# Esquematico.net
KiCad netlist of a schematic drawn in Altium Designer
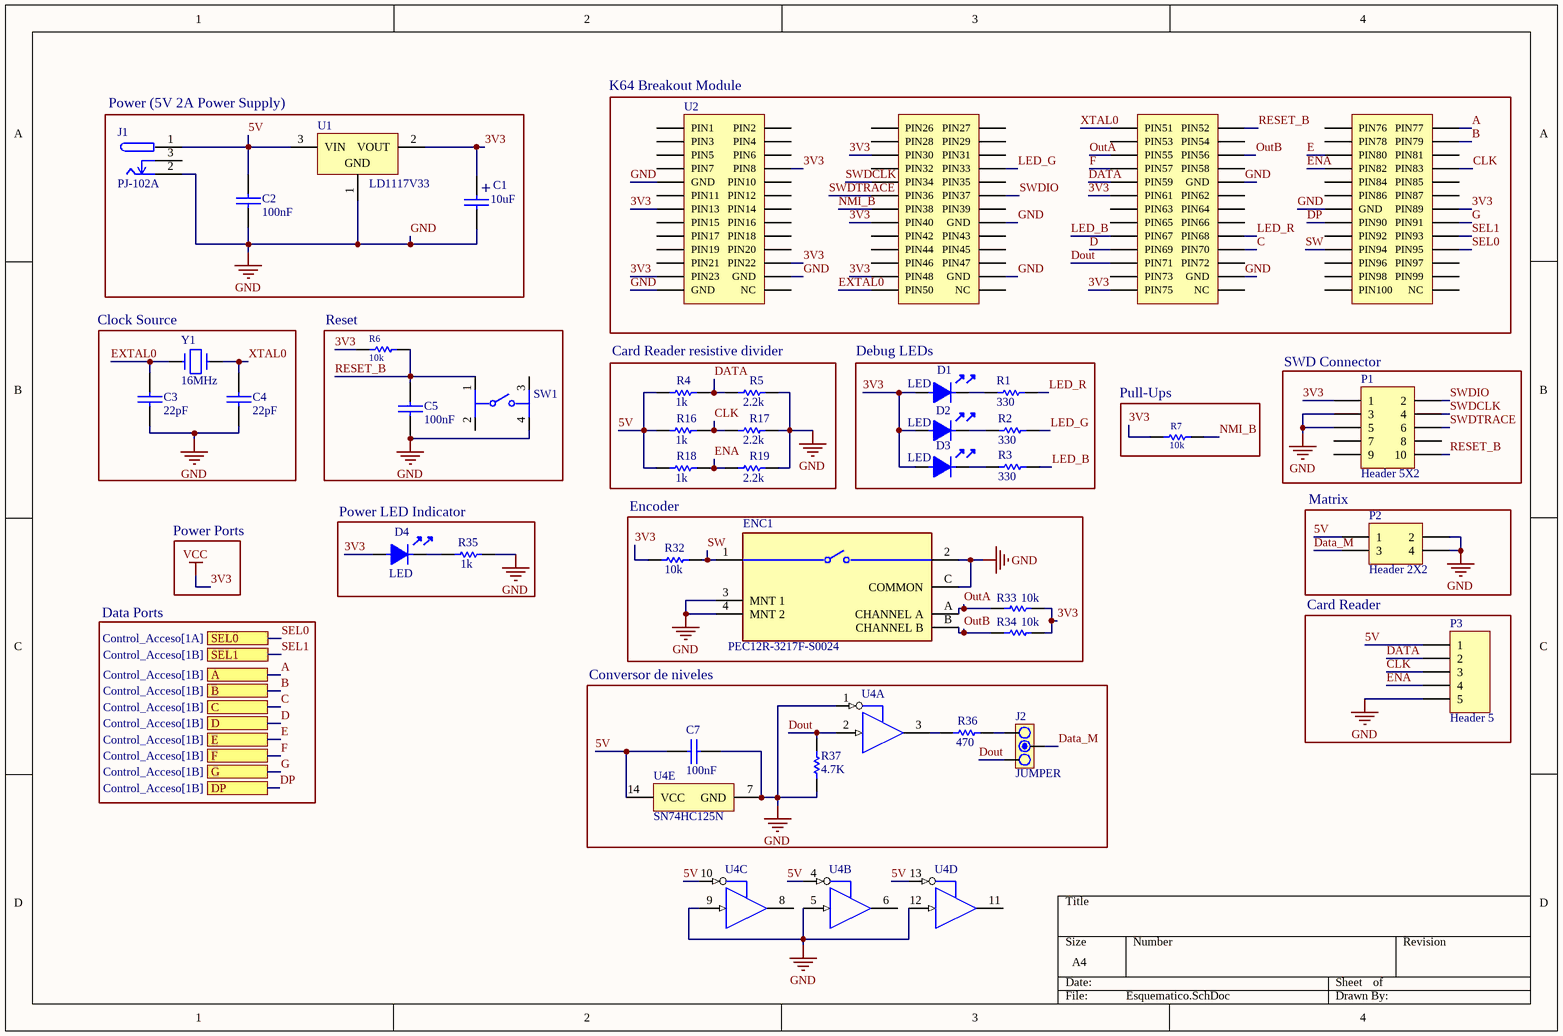
[diagram p0: Esquematico.SchDoc]

(export (version "E")
  (design (tool "Eeschema 10.0.6"))
  (components
    (comp (ref "C1")
      (value "10uF")
      (footprint "CAP100RP")
      (description "Electrolytic Capacitor")
      (libsource (lib "LIB PIO IX") (part "CAPPOL"))
    )
    (comp (ref "C2")
      (value "100nF")
      (footprint "CAP200")
      (description "Multilayer Ceramic Capacitor")
      (libsource (lib "LIB PIO IX") (part "CAP"))
    )
    (comp (ref "C3")
      (value "22pF")
      (footprint "CAP200")
      (description "Multilayer Ceramic Capacitor")
      (libsource (lib "LIB PIO IX") (part "CAP"))
    )
    (comp (ref "C4")
      (value "22pF")
      (footprint "CAP200")
      (description "Multilayer Ceramic Capacitor")
      (libsource (lib "LIB PIO IX") (part "CAP"))
    )
    (comp (ref "C5")
      (value "100nF")
      (footprint "CAP200")
      (description "Multilayer Ceramic Capacitor")
      (libsource (lib "LIB PIO IX") (part "CAP"))
    )
    (comp (ref "C7")
      (value "100nF")
      (footprint "CAP200")
      (description "Multilayer Ceramic Capacitor")
      (libsource (lib "LIB PIO IX") (part "CAP"))
    )
    (comp (ref "D1")
      (value "LED")
      (footprint "LED3")
      (description "3mm LED RED")
      (libsource (lib "LIB PIO IX") (part "LED"))
    )
    (comp (ref "D2")
      (value "LED")
      (footprint "LED3")
      (description "3mm LED GREEN")
      (libsource (lib "LIB PIO IX") (part "LED"))
    )
    (comp (ref "D3")
      (value "LED")
      (footprint "LED3")
      (description "3mm LED BLUE")
      (libsource (lib "LIB PIO IX") (part "LED"))
    )
    (comp (ref "D4")
      (value "LED")
      (footprint "LED3")
      (description "3mm LED RED")
      (libsource (lib "LIB PIO IX") (part "LED"))
    )
    (comp (ref "ENC1")
      (value "PEC12R-3217F-S0024")
      (footprint "FP-PEC12R-3217F-S0024-MFG")
      (description "ROTARY ENCODER")
      (libsource (lib "Altium Content Vault") (part "795c46dd6d7d77f565e7c060d07d204"))
    )
    (comp (ref "J1")
      (value "PJ-102A")
      (footprint "FP-PJ-102A-MFG")
      (description "PJ-102A 2.0 x 6.5 mm, 2.5 A, Horizontal, Through Hole, Tapered Pins, Dc Power Jack Connector")
      (libsource (lib "Altium Content Vault") (part "c639f672d24b5d70918fa8d934b95d1"))
    )
    (comp (ref "J2") (value "JUMPER") (footprint "JUMPER3") (libsource (lib "LIB PIO IX") (part "JUMPER3")))
    (comp (ref "P1")
      (value "Header 5X2")
      (footprint "HDR2X5")
      (description "Header, 5-Pin, Dual row")
      (fields (field (name "PUBLISHER") "Altium Limited"))
      (libsource (lib "Miscellaneous Connectors") (part "Header 5X2"))
    )
    (comp (ref "P2")
      (value "Header 2X2")
      (footprint "HDR2X2")
      (description "Header, 2-Pin, Dual row")
      (fields (field (name "PUBLISHER") "Altium Limited"))
      (libsource (lib "Miscellaneous Connectors") (part "Header 2X2"))
    )
    (comp (ref "P3")
      (value "Header 5")
      (footprint "HDR1X5")
      (description "Header, 5-Pin")
      (fields (field (name "PUBLISHER") "Altium Limited"))
      (libsource (lib "Miscellaneous Connectors") (part "Header 5"))
    )
    (comp (ref "R1")
      (value "330")
      (footprint "RES400")
      (description "Through Hole Resistor 1/8W Carbon Film")
      (libsource (lib "LIB PIO IX") (part "RES"))
    )
    (comp (ref "R2")
      (value "330")
      (footprint "RES400")
      (description "Through Hole Resistor 1/8W Carbon Film")
      (libsource (lib "LIB PIO IX") (part "RES"))
    )
    (comp (ref "R3")
      (value "330")
      (footprint "RES400")
      (description "Through Hole Resistor 1/8W Carbon Film")
      (libsource (lib "LIB PIO IX") (part "RES"))
    )
    (comp (ref "R4")
      (value "1k")
      (footprint "RES400")
      (description "Through Hole Resistor 1/8W Carbon Film")
      (libsource (lib "LIB PIO IX") (part "RES"))
    )
    (comp (ref "R5")
      (value "2.2k")
      (footprint "RES400")
      (description "Through Hole Resistor 1/8W Carbon Film")
      (libsource (lib "LIB PIO IX") (part "RES"))
    )
    (comp (ref "R6")
      (value "10k")
      (footprint "RES400")
      (description "Through Hole Resistor 1/8W Carbon Film")
      (libsource (lib "LIB PIO IX") (part "RES"))
    )
    (comp (ref "R7")
      (value "10k")
      (footprint "RES400")
      (description "Through Hole Resistor 1/8W Carbon Film")
      (libsource (lib "LIB PIO IX") (part "RES"))
    )
    (comp (ref "R16")
      (value "1k")
      (footprint "RES400")
      (description "Through Hole Resistor 1/8W Carbon Film")
      (libsource (lib "LIB PIO IX") (part "RES"))
    )
    (comp (ref "R17")
      (value "2.2k")
      (footprint "RES400")
      (description "Through Hole Resistor 1/8W Carbon Film")
      (libsource (lib "LIB PIO IX") (part "RES"))
    )
    (comp (ref "R18")
      (value "1k")
      (footprint "RES400")
      (description "Through Hole Resistor 1/8W Carbon Film")
      (libsource (lib "LIB PIO IX") (part "RES"))
    )
    (comp (ref "R19")
      (value "2.2k")
      (footprint "RES400")
      (description "Through Hole Resistor 1/8W Carbon Film")
      (libsource (lib "LIB PIO IX") (part "RES"))
    )
    (comp (ref "R32")
      (value "10k")
      (footprint "RES400")
      (description "Through Hole Resistor 1/8W Carbon Film")
      (libsource (lib "LIB PIO IX") (part "RES"))
    )
    (comp (ref "R33")
      (value "10k")
      (footprint "RES400")
      (description "Through Hole Resistor 1/8W Carbon Film")
      (libsource (lib "LIB PIO IX") (part "RES"))
    )
    (comp (ref "R34")
      (value "10k")
      (footprint "RES400")
      (description "Through Hole Resistor 1/8W Carbon Film")
      (libsource (lib "LIB PIO IX") (part "RES"))
    )
    (comp (ref "R35")
      (value "1k")
      (footprint "RES400")
      (description "Through Hole Resistor 1/8W Carbon Film")
      (libsource (lib "LIB PIO IX") (part "RES"))
    )
    (comp (ref "R36")
      (value "470")
      (footprint "RES400")
      (description "Through Hole Resistor 1/8W Carbon Film")
      (libsource (lib "LIB PIO IX") (part "RES"))
    )
    (comp (ref "R37")
      (value "4.7K")
      (footprint "RES400")
      (description "Through Hole Resistor 1/8W Carbon Film")
      (libsource (lib "LIB PIO IX") (part "RES"))
    )
    (comp (ref "SW1")
      (value "~")
      (footprint "FP-B3F-1055-MFG")
      (description "SWITCH TACTILE SPST-NO 0.05A 24V")
      (libsource (lib "Altium Content Vault") (part "b8895f3f4cefb76e1819d2863dba89b"))
    )
    (comp (ref "U1")
      (value "LD1117V33")
      (footprint "TO220")
      (description "Fixed Low Drop Positive Voltage Regulator, 3.3V, 3-Pin TO-220")
      (libsource (lib "Altium Content Vault") (part "PM-REG-LD1117V-SIL3"))
    )
    (comp (ref "U2")
      (value "K64 Breakout Module")
      (footprint "Breakout")
      (description "Breakout Module Socket")
      (libsource (lib "Breakout_Module") (part "Breakout"))
    )
    (comp (ref "U4")
      (value "SN74HC125N")
      (footprint "N0014A")
      (description "Quadruple Bus Buffer Gates With 3-State Outputs, N0014A, TUBE")
      (fields
        (field (name "GENERIC PART NUMBER") "SN74HC125")
        (field (name "MANUFACTURER") "Texas Instruments")
      )
      (libsource (lib "Altium Content Vault") (part "TI-SN74HC125-N0014A-14"))
    )
    (comp (ref "Y1")
      (value "16MHz")
      (footprint "CRISTAL PERFIL")
      (description "Cristal 16MHz")
      (libsource (lib "LIB PIO IX") (part "CRISTAL"))
    )
  )
  (nets
    (net (code "1") (name "/5V") (class "Default")
      (node (ref "C2") (pin "1") (pinfunction "1_1") (pintype "passive"))
      (node (ref "C7") (pin "1") (pinfunction "1_1") (pintype "passive"))
      (node (ref "J1") (pin "1") (pinfunction "1_1") (pintype "passive"))
      (node (ref "P2") (pin "1") (pinfunction "1_1") (pintype "passive"))
      (node (ref "P3") (pin "1") (pinfunction "1_1") (pintype "passive"))
      (node (ref "R16") (pin "1") (pinfunction "1_1") (pintype "passive"))
      (node (ref "R18") (pin "1") (pinfunction "1_1") (pintype "passive"))
      (node (ref "R4") (pin "1") (pinfunction "1_1") (pintype "passive"))
      (node (ref "U1") (pin "3") (pinfunction "VIN_3") (pintype "power_in"))
      (node (ref "U4") (pin "10") (pinfunction "3~{OE}_10") (pintype "input"))
      (node (ref "U4") (pin "13") (pinfunction "4~{OE}_13") (pintype "input"))
      (node (ref "U4") (pin "14") (pinfunction "VCC_14") (pintype "power_in"))
      (node (ref "U4") (pin "4") (pinfunction "2~{OE}_4") (pintype "input"))
    )
    (net (code "2") (name "/A") (class "Default")
      (node (ref "U2") (pin "80") (pinfunction "PIN77_80") (pintype "passive"))
    )
    (net (code "3") (name "/B") (class "Default")
      (node (ref "U2") (pin "82") (pinfunction "PIN79_82") (pintype "passive"))
    )
    (net (code "4") (name "/C") (class "Default")
      (node (ref "U2") (pin "72") (pinfunction "PIN70_72") (pintype "passive"))
    )
    (net (code "5") (name "/CLK") (class "Default")
      (node (ref "P3") (pin "3") (pinfunction "3_3") (pintype "passive"))
      (node (ref "R16") (pin "2") (pinfunction "2_2") (pintype "passive"))
      (node (ref "R17") (pin "1") (pinfunction "1_1") (pintype "passive"))
      (node (ref "U2") (pin "86") (pinfunction "PIN83_86") (pintype "passive"))
    )
    (net (code "6") (name "/D") (class "Default")
      (node (ref "U2") (pin "71") (pinfunction "PIN69_71") (pintype "passive"))
    )
    (net (code "7") (name "/DATA") (class "Default")
      (node (ref "P3") (pin "2") (pinfunction "2_2") (pintype "passive"))
      (node (ref "R4") (pin "2") (pinfunction "2_2") (pintype "passive"))
      (node (ref "R5") (pin "1") (pinfunction "1_1") (pintype "passive"))
      (node (ref "U2") (pin "61") (pinfunction "PIN59_61") (pintype "passive"))
    )
    (net (code "8") (name "/DP") (class "Default")
      (node (ref "U2") (pin "93") (pinfunction "PIN90_93") (pintype "passive"))
    )
    (net (code "9") (name "/Data_M") (class "Default")
      (node (ref "J2") (pin "2") (pinfunction "2_2") (pintype "passive"))
      (node (ref "P2") (pin "3") (pinfunction "3_3") (pintype "passive"))
    )
    (net (code "10") (name "/Dout") (class "Default")
      (node (ref "J2") (pin "1") (pinfunction "1_1") (pintype "passive"))
      (node (ref "R37") (pin "2") (pinfunction "2_2") (pintype "passive"))
      (node (ref "U2") (pin "73") (pinfunction "PIN71_73") (pintype "passive"))
      (node (ref "U4") (pin "2") (pinfunction "1A_2") (pintype "input"))
    )
    (net (code "11") (name "/E") (class "Default")
      (node (ref "U2") (pin "83") (pinfunction "PIN80_83") (pintype "passive"))
    )
    (net (code "12") (name "/ENA") (class "Default")
      (node (ref "P3") (pin "4") (pinfunction "4_4") (pintype "passive"))
      (node (ref "R18") (pin "2") (pinfunction "2_2") (pintype "passive"))
      (node (ref "R19") (pin "1") (pinfunction "1_1") (pintype "passive"))
      (node (ref "U2") (pin "85") (pinfunction "PIN82_85") (pintype "passive"))
    )
    (net (code "13") (name "/EXTAL0") (class "Default")
      (node (ref "C3") (pin "1") (pinfunction "1_1") (pintype "passive"))
      (node (ref "U2") (pin "51") (pinfunction "PIN50_51") (pintype "passive"))
      (node (ref "Y1") (pin "1") (pinfunction "1_1") (pintype "passive"))
    )
    (net (code "14") (name "/F") (class "Default")
      (node (ref "U2") (pin "59") (pinfunction "PIN57_59") (pintype "passive"))
    )
    (net (code "15") (name "/G") (class "Default")
      (node (ref "U2") (pin "94") (pinfunction "PIN91_94") (pintype "passive"))
    )
    (net (code "16") (name "/LED_B") (class "Default")
      (node (ref "R3") (pin "2") (pinfunction "2_2") (pintype "passive"))
      (node (ref "U2") (pin "69") (pinfunction "PIN67_69") (pintype "passive"))
    )
    (net (code "17") (name "/LED_G") (class "Default")
      (node (ref "R2") (pin "2") (pinfunction "2_2") (pintype "passive"))
      (node (ref "U2") (pin "34") (pinfunction "PIN33_34") (pintype "passive"))
    )
    (net (code "18") (name "/LED_R") (class "Default")
      (node (ref "R1") (pin "2") (pinfunction "2_2") (pintype "passive"))
      (node (ref "U2") (pin "70") (pinfunction "PIN68_70") (pintype "passive"))
    )
    (net (code "19") (name "/NMI_B") (class "Default")
      (node (ref "R7") (pin "1") (pinfunction "1_1") (pintype "passive"))
      (node (ref "U2") (pin "39") (pinfunction "PIN38_39") (pintype "passive"))
    )
    (net (code "20") (name "/OutA") (class "Default")
      (node (ref "ENC1") (pin "A") (pinfunction "CHANNEL_A_A") (pintype "passive"))
      (node (ref "R33") (pin "1") (pinfunction "1_1") (pintype "passive"))
      (node (ref "U2") (pin "57") (pinfunction "PIN55_57") (pintype "passive"))
    )
    (net (code "21") (name "/OutB") (class "Default")
      (node (ref "ENC1") (pin "B") (pinfunction "CHANNEL_B_B") (pintype "passive"))
      (node (ref "R34") (pin "2") (pinfunction "2_2") (pintype "passive"))
      (node (ref "U2") (pin "58") (pinfunction "PIN56_58") (pintype "passive"))
    )
    (net (code "22") (name "/RESET_B") (class "Default")
      (node (ref "C5") (pin "1") (pinfunction "1_1") (pintype "passive"))
      (node (ref "P1") (pin "10") (pinfunction "10_10") (pintype "passive"))
      (node (ref "R6") (pin "1") (pinfunction "1_1") (pintype "passive"))
      (node (ref "SW1") (pin "1") (pinfunction "1_1") (pintype "passive"))
      (node (ref "U2") (pin "54") (pinfunction "PIN52_54") (pintype "passive"))
    )
    (net (code "23") (name "/SEL0") (class "Default")
      (node (ref "U2") (pin "98") (pinfunction "PIN95_98") (pintype "passive"))
    )
    (net (code "24") (name "/SEL1") (class "Default")
      (node (ref "U2") (pin "96") (pinfunction "PIN93_96") (pintype "passive"))
    )
    (net (code "25") (name "/SW") (class "Default")
      (node (ref "ENC1") (pin "1") (pinfunction "1_1") (pintype "passive"))
      (node (ref "R32") (pin "2") (pinfunction "2_2") (pintype "passive"))
      (node (ref "U2") (pin "97") (pinfunction "PIN94_97") (pintype "passive"))
    )
    (net (code "26") (name "/SWDCLK") (class "Default")
      (node (ref "P1") (pin "4") (pinfunction "4_4") (pintype "passive"))
      (node (ref "U2") (pin "35") (pinfunction "PIN34_35") (pintype "passive"))
    )
    (net (code "27") (name "/SWDIO") (class "Default")
      (node (ref "P1") (pin "2") (pinfunction "2_2") (pintype "passive"))
      (node (ref "U2") (pin "38") (pinfunction "PIN37_38") (pintype "passive"))
    )
    (net (code "28") (name "/SWDTRACE") (class "Default")
      (node (ref "P1") (pin "6") (pinfunction "6_6") (pintype "passive"))
      (node (ref "U2") (pin "37") (pinfunction "PIN36_37") (pintype "passive"))
    )
    (net (code "29") (name "/XTAL0") (class "Default")
      (node (ref "C4") (pin "1") (pinfunction "1_1") (pintype "passive"))
      (node (ref "U2") (pin "53") (pinfunction "PIN51_53") (pintype "passive"))
      (node (ref "Y1") (pin "2") (pinfunction "10_2") (pintype "passive"))
    )
    (net (code "30") (name "GND") (class "Default")
      (node (ref "C1") (pin "2") (pinfunction "2_2") (pintype "passive"))
      (node (ref "C2") (pin "2") (pinfunction "2_2") (pintype "passive"))
      (node (ref "C3") (pin "2") (pinfunction "2_2") (pintype "passive"))
      (node (ref "C4") (pin "2") (pinfunction "2_2") (pintype "passive"))
      (node (ref "C5") (pin "2") (pinfunction "2_2") (pintype "passive"))
      (node (ref "C7") (pin "2") (pinfunction "2_2") (pintype "passive"))
      (node (ref "ENC1") (pin "2") (pinfunction "2_2") (pintype "passive"))
      (node (ref "ENC1") (pin "3") (pinfunction "MNT_1_3") (pintype "passive"))
      (node (ref "ENC1") (pin "4") (pinfunction "MNT_2_4") (pintype "passive"))
      (node (ref "ENC1") (pin "C") (pinfunction "COMMON_C") (pintype "passive"))
      (node (ref "J1") (pin "2") (pinfunction "2_2") (pintype "passive"))
      (node (ref "P1") (pin "3") (pinfunction "3_3") (pintype "passive"))
      (node (ref "P1") (pin "5") (pinfunction "5_5") (pintype "passive"))
      (node (ref "P2") (pin "2") (pinfunction "2_2") (pintype "passive"))
      (node (ref "P2") (pin "4") (pinfunction "4_4") (pintype "passive"))
      (node (ref "P3") (pin "5") (pinfunction "5_5") (pintype "passive"))
      (node (ref "R17") (pin "2") (pinfunction "2_2") (pintype "passive"))
      (node (ref "R19") (pin "2") (pinfunction "2_2") (pintype "passive"))
      (node (ref "R35") (pin "2") (pinfunction "2_2") (pintype "passive"))
      (node (ref "R37") (pin "1") (pinfunction "1_1") (pintype "passive"))
      (node (ref "R5") (pin "2") (pinfunction "2_2") (pintype "passive"))
      (node (ref "SW1") (pin "4") (pinfunction "4_4") (pintype "passive"))
      (node (ref "U1") (pin "1") (pinfunction "GND_1") (pintype "power_in"))
      (node (ref "U2") (pin "24") (pinfunction "GND_24") (pintype "passive"))
      (node (ref "U2") (pin "25") (pinfunction "GND_25") (pintype "passive"))
      (node (ref "U2") (pin "42") (pinfunction "GND_42") (pintype "passive"))
      (node (ref "U2") (pin "50") (pinfunction "GND_50") (pintype "passive"))
      (node (ref "U2") (pin "62") (pinfunction "GND_62") (pintype "passive"))
      (node (ref "U2") (pin "76") (pinfunction "GND_76") (pintype "passive"))
      (node (ref "U2") (pin "9") (pinfunction "GND_9") (pintype "passive"))
      (node (ref "U2") (pin "91") (pinfunction "GND_91") (pintype "passive"))
      (node (ref "U4") (pin "1") (pinfunction "1~{OE}_1") (pintype "input"))
      (node (ref "U4") (pin "12") (pinfunction "4A_12") (pintype "input"))
      (node (ref "U4") (pin "5") (pinfunction "2A_5") (pintype "input"))
      (node (ref "U4") (pin "7") (pinfunction "GND_7") (pintype "power_in"))
      (node (ref "U4") (pin "9") (pinfunction "3A_9") (pintype "input"))
    )
    (net (code "31") (name "Net-(D1-Pad2)") (class "Default")
      (node (ref "D1") (pin "2") (pinfunction "2_2") (pintype "passive"))
      (node (ref "R1") (pin "1") (pinfunction "1_1") (pintype "passive"))
    )
    (net (code "32") (name "Net-(D2-Pad2)") (class "Default")
      (node (ref "D2") (pin "2") (pinfunction "2_2") (pintype "passive"))
      (node (ref "R2") (pin "1") (pinfunction "1_1") (pintype "passive"))
    )
    (net (code "33") (name "Net-(D3-Pad2)") (class "Default")
      (node (ref "D3") (pin "2") (pinfunction "2_2") (pintype "passive"))
      (node (ref "R3") (pin "1") (pinfunction "1_1") (pintype "passive"))
    )
    (net (code "34") (name "Net-(D4-Pad2)") (class "Default")
      (node (ref "D4") (pin "2") (pinfunction "2_2") (pintype "passive"))
      (node (ref "R35") (pin "1") (pinfunction "1_1") (pintype "passive"))
    )
    (net (code "35") (name "Net-(J2-Pad3)") (class "Default")
      (node (ref "J2") (pin "3") (pinfunction "3_3") (pintype "passive"))
      (node (ref "R36") (pin "1") (pinfunction "1_1") (pintype "passive"))
    )
    (net (code "36") (name "Net-(U4A-1Y)") (class "Default")
      (node (ref "R36") (pin "2") (pinfunction "2_2") (pintype "passive"))
      (node (ref "U4") (pin "3") (pinfunction "1Y_3") (pintype "tri_state"))
    )
    (net (code "37") (name "VCC") (class "Default")
      (node (ref "C1") (pin "1") (pinfunction "1_1") (pintype "passive"))
      (node (ref "D1") (pin "1") (pinfunction "1_1") (pintype "passive"))
      (node (ref "D2") (pin "1") (pinfunction "1_1") (pintype "passive"))
      (node (ref "D3") (pin "1") (pinfunction "1_1") (pintype "passive"))
      (node (ref "D4") (pin "1") (pinfunction "1_1") (pintype "passive"))
      (node (ref "P1") (pin "1") (pinfunction "1_1") (pintype "passive"))
      (node (ref "R32") (pin "1") (pinfunction "1_1") (pintype "passive"))
      (node (ref "R33") (pin "2") (pinfunction "2_2") (pintype "passive"))
      (node (ref "R34") (pin "1") (pinfunction "1_1") (pintype "passive"))
      (node (ref "R6") (pin "2") (pinfunction "2_2") (pintype "passive"))
      (node (ref "R7") (pin "2") (pinfunction "2_2") (pintype "passive"))
      (node (ref "U1") (pin "2") (pinfunction "VOUT_2") (pintype "power_in"))
      (node (ref "U2") (pin "13") (pinfunction "PIN13_13") (pintype "passive"))
      (node (ref "U2") (pin "22") (pinfunction "PIN22_22") (pintype "passive"))
      (node (ref "U2") (pin "23") (pinfunction "PIN23_23") (pintype "passive"))
      (node (ref "U2") (pin "31") (pinfunction "PIN30_31") (pintype "passive"))
      (node (ref "U2") (pin "41") (pinfunction "PIN40_41") (pintype "passive"))
      (node (ref "U2") (pin "49") (pinfunction "PIN48_49") (pintype "passive"))
      (node (ref "U2") (pin "63") (pinfunction "PIN61_63") (pintype "passive"))
      (node (ref "U2") (pin "77") (pinfunction "PIN75_77") (pintype "passive"))
      (node (ref "U2") (pin "8") (pinfunction "PIN8_8") (pintype "passive"))
      (node (ref "U2") (pin "92") (pinfunction "PIN89_92") (pintype "passive"))
    )
    (net (code "38") (name "unconnected-(J1-Pad3)") (class "Default")
      (node (ref "J1") (pin "3") (pinfunction "3_3") (pintype "passive"))
    )
    (net (code "39") (name "unconnected-(P1-Pad7)") (class "Default")
      (node (ref "P1") (pin "7") (pinfunction "7_7") (pintype "passive"))
    )
    (net (code "40") (name "unconnected-(P1-Pad8)") (class "Default")
      (node (ref "P1") (pin "8") (pinfunction "8_8") (pintype "passive"))
    )
    (net (code "41") (name "unconnected-(P1-Pad9)") (class "Default")
      (node (ref "P1") (pin "9") (pinfunction "9_9") (pintype "passive"))
    )
    (net (code "42") (name "unconnected-(SW1-Pad2)") (class "Default")
      (node (ref "SW1") (pin "2") (pinfunction "2_2") (pintype "passive"))
    )
    (net (code "43") (name "unconnected-(SW1-Pad3)") (class "Default")
      (node (ref "SW1") (pin "3") (pinfunction "3_3") (pintype "passive"))
    )
    (net (code "44") (name "unconnected-(U2-NC-Pad26)") (class "Default")
      (node (ref "U2") (pin "26") (pinfunction "NC_26") (pintype "passive"))
    )
    (net (code "45") (name "unconnected-(U2-NC-Pad52)") (class "Default")
      (node (ref "U2") (pin "52") (pinfunction "NC_52") (pintype "passive"))
    )
    (net (code "46") (name "unconnected-(U2-NC-Pad78)") (class "Default")
      (node (ref "U2") (pin "78") (pinfunction "NC_78") (pintype "passive"))
    )
    (net (code "47") (name "unconnected-(U2-NC-Pad104)") (class "Default")
      (node (ref "U2") (pin "104") (pinfunction "NC_104") (pintype "passive"))
    )
    (net (code "48") (name "unconnected-(U2-PIN1-Pad1)") (class "Default")
      (node (ref "U2") (pin "1") (pinfunction "PIN1_1") (pintype "passive"))
    )
    (net (code "49") (name "unconnected-(U2-PIN2-Pad2)") (class "Default")
      (node (ref "U2") (pin "2") (pinfunction "PIN2_2") (pintype "passive"))
    )
    (net (code "50") (name "unconnected-(U2-PIN3-Pad3)") (class "Default")
      (node (ref "U2") (pin "3") (pinfunction "PIN3_3") (pintype "passive"))
    )
    (net (code "51") (name "unconnected-(U2-PIN4-Pad4)") (class "Default")
      (node (ref "U2") (pin "4") (pinfunction "PIN4_4") (pintype "passive"))
    )
    (net (code "52") (name "unconnected-(U2-PIN5-Pad5)") (class "Default")
      (node (ref "U2") (pin "5") (pinfunction "PIN5_5") (pintype "passive"))
    )
    (net (code "53") (name "unconnected-(U2-PIN6-Pad6)") (class "Default")
      (node (ref "U2") (pin "6") (pinfunction "PIN6_6") (pintype "passive"))
    )
    (net (code "54") (name "unconnected-(U2-PIN7-Pad7)") (class "Default")
      (node (ref "U2") (pin "7") (pinfunction "PIN7_7") (pintype "passive"))
    )
    (net (code "55") (name "unconnected-(U2-PIN10-Pad10)") (class "Default")
      (node (ref "U2") (pin "10") (pinfunction "PIN10_10") (pintype "passive"))
    )
    (net (code "56") (name "unconnected-(U2-PIN11-Pad11)") (class "Default")
      (node (ref "U2") (pin "11") (pinfunction "PIN11_11") (pintype "passive"))
    )
    (net (code "57") (name "unconnected-(U2-PIN12-Pad12)") (class "Default")
      (node (ref "U2") (pin "12") (pinfunction "PIN12_12") (pintype "passive"))
    )
    (net (code "58") (name "unconnected-(U2-PIN14-Pad14)") (class "Default")
      (node (ref "U2") (pin "14") (pinfunction "PIN14_14") (pintype "passive"))
    )
    (net (code "59") (name "unconnected-(U2-PIN15-Pad15)") (class "Default")
      (node (ref "U2") (pin "15") (pinfunction "PIN15_15") (pintype "passive"))
    )
    (net (code "60") (name "unconnected-(U2-PIN16-Pad16)") (class "Default")
      (node (ref "U2") (pin "16") (pinfunction "PIN16_16") (pintype "passive"))
    )
    (net (code "61") (name "unconnected-(U2-PIN17-Pad17)") (class "Default")
      (node (ref "U2") (pin "17") (pinfunction "PIN17_17") (pintype "passive"))
    )
    (net (code "62") (name "unconnected-(U2-PIN18-Pad18)") (class "Default")
      (node (ref "U2") (pin "18") (pinfunction "PIN18_18") (pintype "passive"))
    )
    (net (code "63") (name "unconnected-(U2-PIN19-Pad19)") (class "Default")
      (node (ref "U2") (pin "19") (pinfunction "PIN19_19") (pintype "passive"))
    )
    (net (code "64") (name "unconnected-(U2-PIN20-Pad20)") (class "Default")
      (node (ref "U2") (pin "20") (pinfunction "PIN20_20") (pintype "passive"))
    )
    (net (code "65") (name "unconnected-(U2-PIN21-Pad21)") (class "Default")
      (node (ref "U2") (pin "21") (pinfunction "PIN21_21") (pintype "passive"))
    )
    (net (code "66") (name "unconnected-(U2-PIN26-Pad27)") (class "Default")
      (node (ref "U2") (pin "27") (pinfunction "PIN26_27") (pintype "passive"))
    )
    (net (code "67") (name "unconnected-(U2-PIN27-Pad28)") (class "Default")
      (node (ref "U2") (pin "28") (pinfunction "PIN27_28") (pintype "passive"))
    )
    (net (code "68") (name "unconnected-(U2-PIN28-Pad29)") (class "Default")
      (node (ref "U2") (pin "29") (pinfunction "PIN28_29") (pintype "passive"))
    )
    (net (code "69") (name "unconnected-(U2-PIN29-Pad30)") (class "Default")
      (node (ref "U2") (pin "30") (pinfunction "PIN29_30") (pintype "passive"))
    )
    (net (code "70") (name "unconnected-(U2-PIN31-Pad32)") (class "Default")
      (node (ref "U2") (pin "32") (pinfunction "PIN31_32") (pintype "passive"))
    )
    (net (code "71") (name "unconnected-(U2-PIN32-Pad33)") (class "Default")
      (node (ref "U2") (pin "33") (pinfunction "PIN32_33") (pintype "passive"))
    )
    (net (code "72") (name "unconnected-(U2-PIN35-Pad36)") (class "Default")
      (node (ref "U2") (pin "36") (pinfunction "PIN35_36") (pintype "passive"))
    )
    (net (code "73") (name "unconnected-(U2-PIN39-Pad40)") (class "Default")
      (node (ref "U2") (pin "40") (pinfunction "PIN39_40") (pintype "passive"))
    )
    (net (code "74") (name "unconnected-(U2-PIN42-Pad43)") (class "Default")
      (node (ref "U2") (pin "43") (pinfunction "PIN42_43") (pintype "passive"))
    )
    (net (code "75") (name "unconnected-(U2-PIN43-Pad44)") (class "Default")
      (node (ref "U2") (pin "44") (pinfunction "PIN43_44") (pintype "passive"))
    )
    (net (code "76") (name "unconnected-(U2-PIN44-Pad45)") (class "Default")
      (node (ref "U2") (pin "45") (pinfunction "PIN44_45") (pintype "passive"))
    )
    (net (code "77") (name "unconnected-(U2-PIN45-Pad46)") (class "Default")
      (node (ref "U2") (pin "46") (pinfunction "PIN45_46") (pintype "passive"))
    )
    (net (code "78") (name "unconnected-(U2-PIN46-Pad47)") (class "Default")
      (node (ref "U2") (pin "47") (pinfunction "PIN46_47") (pintype "passive"))
    )
    (net (code "79") (name "unconnected-(U2-PIN47-Pad48)") (class "Default")
      (node (ref "U2") (pin "48") (pinfunction "PIN47_48") (pintype "passive"))
    )
    (net (code "80") (name "unconnected-(U2-PIN53-Pad55)") (class "Default")
      (node (ref "U2") (pin "55") (pinfunction "PIN53_55") (pintype "passive"))
    )
    (net (code "81") (name "unconnected-(U2-PIN54-Pad56)") (class "Default")
      (node (ref "U2") (pin "56") (pinfunction "PIN54_56") (pintype "passive"))
    )
    (net (code "82") (name "unconnected-(U2-PIN58-Pad60)") (class "Default")
      (node (ref "U2") (pin "60") (pinfunction "PIN58_60") (pintype "passive"))
    )
    (net (code "83") (name "unconnected-(U2-PIN62-Pad64)") (class "Default")
      (node (ref "U2") (pin "64") (pinfunction "PIN62_64") (pintype "passive"))
    )
    (net (code "84") (name "unconnected-(U2-PIN63-Pad65)") (class "Default")
      (node (ref "U2") (pin "65") (pinfunction "PIN63_65") (pintype "passive"))
    )
    (net (code "85") (name "unconnected-(U2-PIN64-Pad66)") (class "Default")
      (node (ref "U2") (pin "66") (pinfunction "PIN64_66") (pintype "passive"))
    )
    (net (code "86") (name "unconnected-(U2-PIN65-Pad67)") (class "Default")
      (node (ref "U2") (pin "67") (pinfunction "PIN65_67") (pintype "passive"))
    )
    (net (code "87") (name "unconnected-(U2-PIN66-Pad68)") (class "Default")
      (node (ref "U2") (pin "68") (pinfunction "PIN66_68") (pintype "passive"))
    )
    (net (code "88") (name "unconnected-(U2-PIN72-Pad74)") (class "Default")
      (node (ref "U2") (pin "74") (pinfunction "PIN72_74") (pintype "passive"))
    )
    (net (code "89") (name "unconnected-(U2-PIN73-Pad75)") (class "Default")
      (node (ref "U2") (pin "75") (pinfunction "PIN73_75") (pintype "passive"))
    )
    (net (code "90") (name "unconnected-(U2-PIN76-Pad79)") (class "Default")
      (node (ref "U2") (pin "79") (pinfunction "PIN76_79") (pintype "passive"))
    )
    (net (code "91") (name "unconnected-(U2-PIN78-Pad81)") (class "Default")
      (node (ref "U2") (pin "81") (pinfunction "PIN78_81") (pintype "passive"))
    )
    (net (code "92") (name "unconnected-(U2-PIN81-Pad84)") (class "Default")
      (node (ref "U2") (pin "84") (pinfunction "PIN81_84") (pintype "passive"))
    )
    (net (code "93") (name "unconnected-(U2-PIN84-Pad87)") (class "Default")
      (node (ref "U2") (pin "87") (pinfunction "PIN84_87") (pintype "passive"))
    )
    (net (code "94") (name "unconnected-(U2-PIN85-Pad88)") (class "Default")
      (node (ref "U2") (pin "88") (pinfunction "PIN85_88") (pintype "passive"))
    )
    (net (code "95") (name "unconnected-(U2-PIN86-Pad89)") (class "Default")
      (node (ref "U2") (pin "89") (pinfunction "PIN86_89") (pintype "passive"))
    )
    (net (code "96") (name "unconnected-(U2-PIN87-Pad90)") (class "Default")
      (node (ref "U2") (pin "90") (pinfunction "PIN87_90") (pintype "passive"))
    )
    (net (code "97") (name "unconnected-(U2-PIN92-Pad95)") (class "Default")
      (node (ref "U2") (pin "95") (pinfunction "PIN92_95") (pintype "passive"))
    )
    (net (code "98") (name "unconnected-(U2-PIN96-Pad99)") (class "Default")
      (node (ref "U2") (pin "99") (pinfunction "PIN96_99") (pintype "passive"))
    )
    (net (code "99") (name "unconnected-(U2-PIN97-Pad100)") (class "Default")
      (node (ref "U2") (pin "100") (pinfunction "PIN97_100") (pintype "passive"))
    )
    (net (code "100") (name "unconnected-(U2-PIN98-Pad101)") (class "Default")
      (node (ref "U2") (pin "101") (pinfunction "PIN98_101") (pintype "passive"))
    )
    (net (code "101") (name "unconnected-(U2-PIN99-Pad102)") (class "Default")
      (node (ref "U2") (pin "102") (pinfunction "PIN99_102") (pintype "passive"))
    )
    (net (code "102") (name "unconnected-(U2-PIN100-Pad103)") (class "Default")
      (node (ref "U2") (pin "103") (pinfunction "PIN100_103") (pintype "passive"))
    )
    (net (code "103") (name "unconnected-(U4B-2Y-Pad6)") (class "Default")
      (node (ref "U4") (pin "6") (pinfunction "2Y_6") (pintype "tri_state"))
    )
    (net (code "104") (name "unconnected-(U4C-3Y-Pad8)") (class "Default")
      (node (ref "U4") (pin "8") (pinfunction "3Y_8") (pintype "tri_state"))
    )
    (net (code "105") (name "unconnected-(U4D-4Y-Pad11)") (class "Default")
      (node (ref "U4") (pin "11") (pinfunction "4Y_11") (pintype "tri_state"))
    )
  )
)
